# DK_D1_RS232_V5.net
KiCad netlist of a schematic drawn in EAGLE
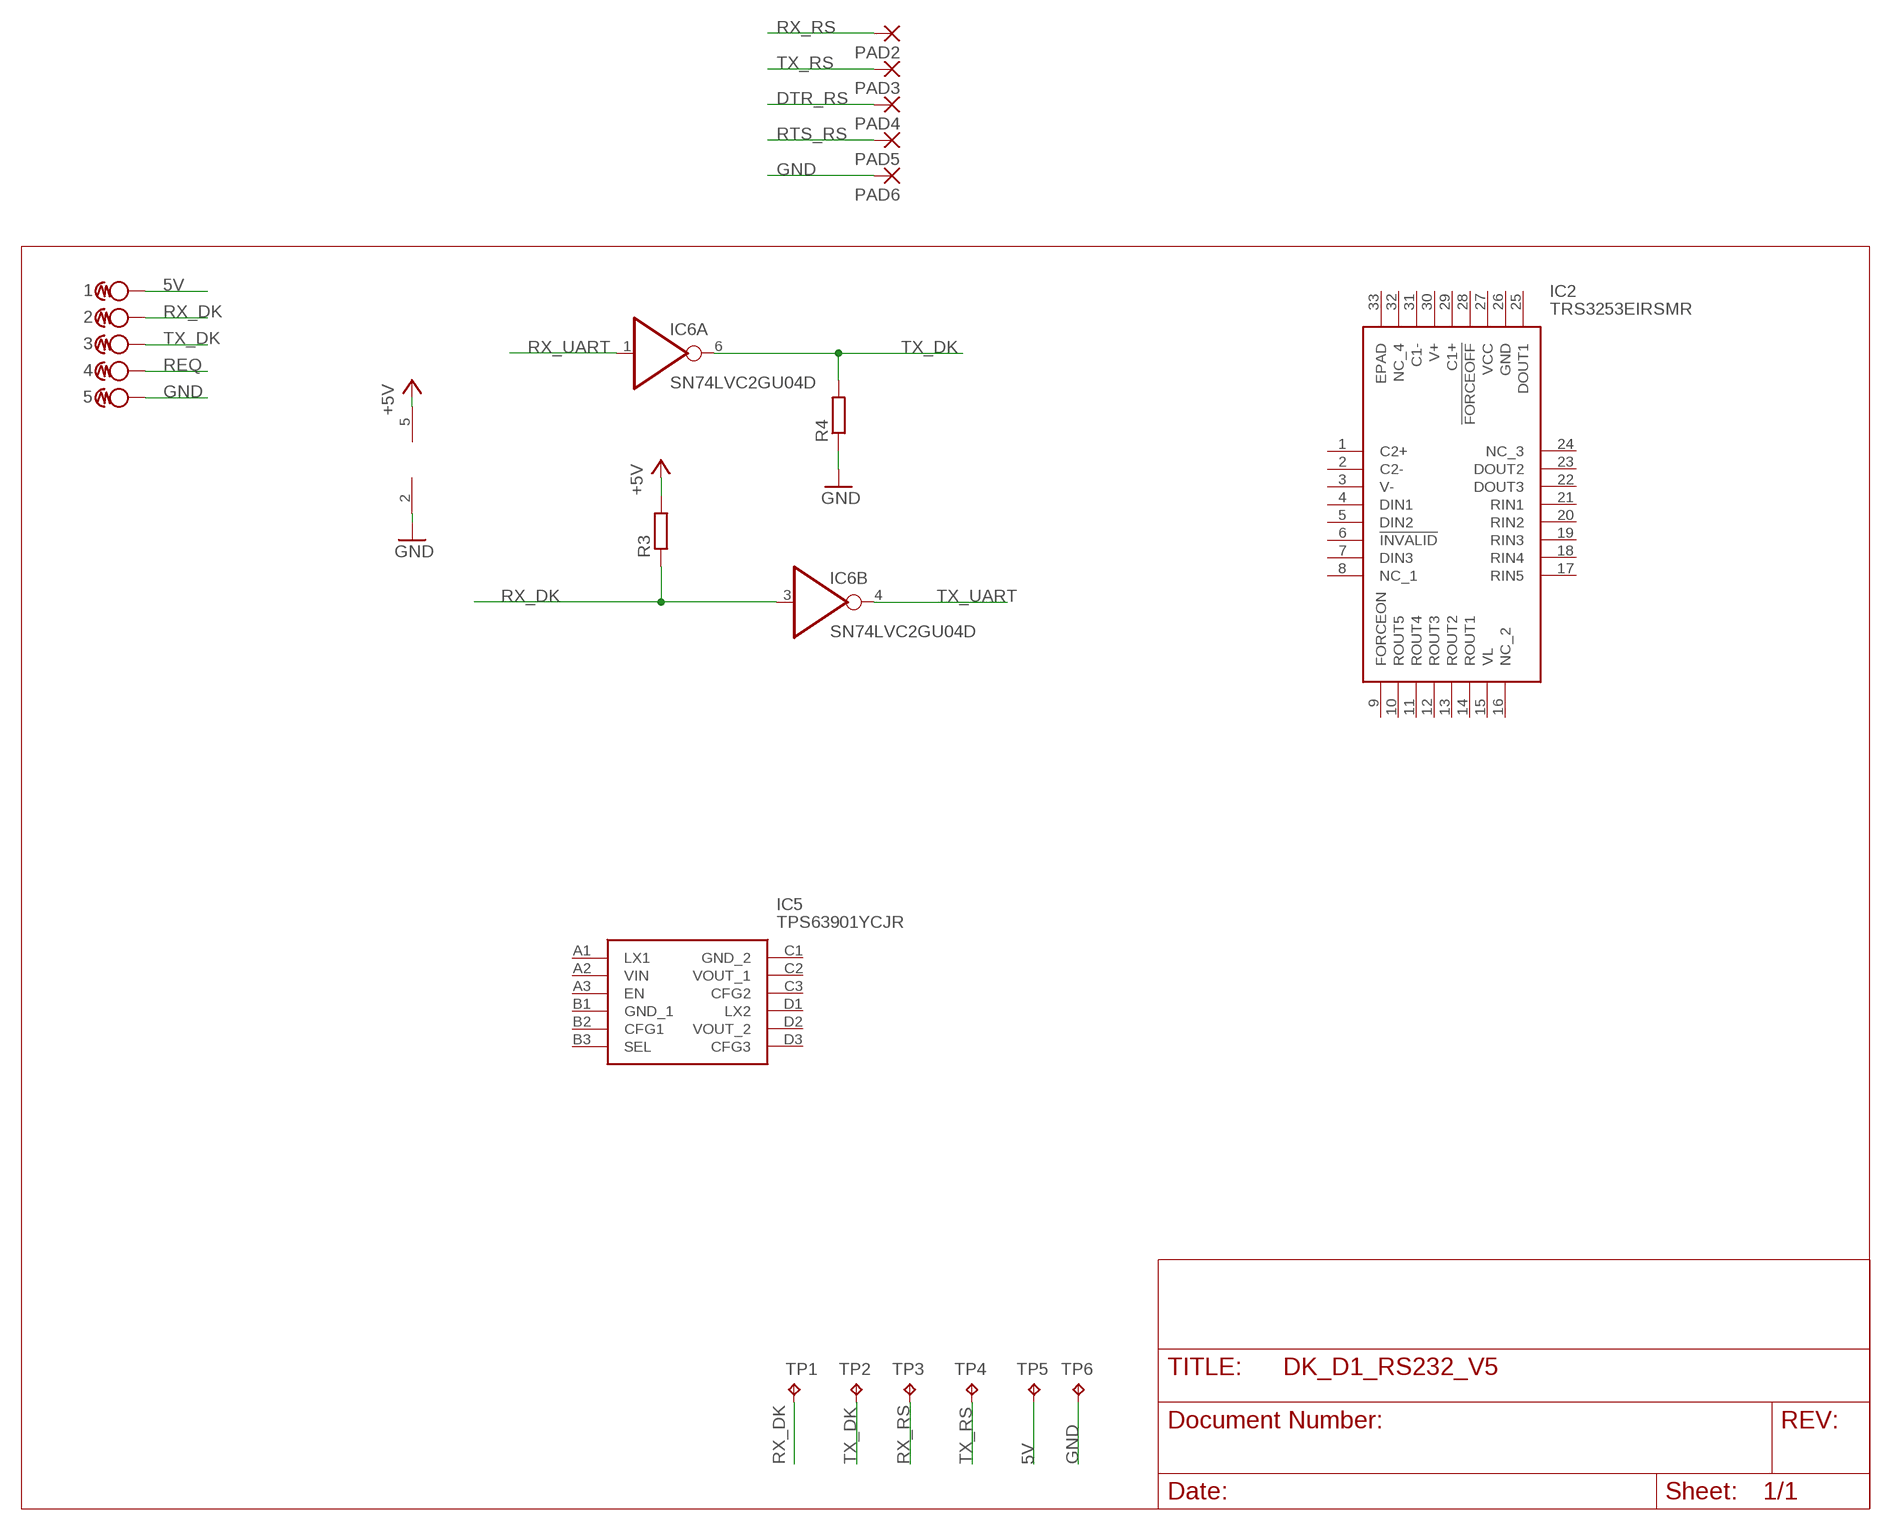
[diagram p0: schematic, sheet 1]

(export (version "E")
  (design (tool "Eeschema 10.0.6"))
  (components
    (comp (ref "1")
      (value "0975-0-15-20-80-14-11-0")
      (footprint "eagle-import:0975-0-15-20-80-14-11-0")
      (libsource (lib "eagle-import") (part "0975-0-15-20-80-14-11-0"))
    )
    (comp (ref "2")
      (value "0975-0-15-20-80-14-11-0")
      (footprint "eagle-import:0975-0-15-20-80-14-11-0")
      (libsource (lib "eagle-import") (part "0975-0-15-20-80-14-11-0"))
    )
    (comp (ref "3")
      (value "0975-0-15-20-80-14-11-0")
      (footprint "eagle-import:0975-0-15-20-80-14-11-0")
      (libsource (lib "eagle-import") (part "0975-0-15-20-80-14-11-0"))
    )
    (comp (ref "4")
      (value "0975-0-15-20-80-14-11-0")
      (footprint "eagle-import:0975-0-15-20-80-14-11-0")
      (libsource (lib "eagle-import") (part "0975-0-15-20-80-14-11-0"))
    )
    (comp (ref "5")
      (value "0975-0-15-20-80-14-11-0")
      (footprint "eagle-import:0975-0-15-20-80-14-11-0")
      (libsource (lib "eagle-import") (part "0975-0-15-20-80-14-11-0"))
    )
    (comp (ref "IC2")
      (value "TRS3253EIRSMR")
      (footprint "eagle-import:QFN40P400X400X100-33N")
      (fields (field (name "MOUSER_PART_NUMBER") "595-TRS3253EIRSMR"))
      (libsource (lib "eagle-import") (part "TRS3253EIRSMR"))
    )
    (comp (ref "IC5")
      (value "TPS63901YCJR")
      (footprint "eagle-import:BGA12C35P3X4_111X146X35")
      (fields (field (name "MOUSER_PART_NUMBER") "595-TPS63901YCJR"))
      (libsource (lib "eagle-import") (part "TPS63901YCJR"))
    )
    (comp (ref "IC6")
      (value "SN74LVC2GU04D")
      (footprint "eagle-import:DBV6")
      (libsource (lib "eagle-import") (part "SN74LVC2GU04D"))
    )
    (comp (ref "PAD2")
      (value "1,6/0,8")
      (footprint "eagle-import:1,6_0,8")
      (libsource (lib "eagle-import") (part "1,6/0,8"))
    )
    (comp (ref "PAD3")
      (value "1,6/0,8")
      (footprint "eagle-import:1,6_0,8")
      (libsource (lib "eagle-import") (part "1,6/0,8"))
    )
    (comp (ref "PAD4")
      (value "1,6/0,8")
      (footprint "eagle-import:1,6_0,8")
      (libsource (lib "eagle-import") (part "1,6/0,8"))
    )
    (comp (ref "PAD5")
      (value "1,6/0,8")
      (footprint "eagle-import:1,6_0,8")
      (libsource (lib "eagle-import") (part "1,6/0,8"))
    )
    (comp (ref "PAD6")
      (value "1,6/0,8")
      (footprint "eagle-import:1,6_0,8")
      (libsource (lib "eagle-import") (part "1,6/0,8"))
    )
    (comp (ref "R3")
      (value "R-EU_R0603")
      (footprint "eagle-import:R0603")
      (libsource (lib "eagle-import") (part "R-EU_R0603"))
    )
    (comp (ref "R4")
      (value "R-EU_R0603")
      (footprint "eagle-import:R0603")
      (libsource (lib "eagle-import") (part "R-EU_R0603"))
    )
    (comp (ref "TP1")
      (value "TPB1,27")
      (footprint "eagle-import:B1,27")
      (libsource (lib "eagle-import") (part "TPB1,27"))
    )
    (comp (ref "TP2")
      (value "TPB1,27")
      (footprint "eagle-import:B1,27")
      (libsource (lib "eagle-import") (part "TPB1,27"))
    )
    (comp (ref "TP3")
      (value "TPB1,27")
      (footprint "eagle-import:B1,27")
      (libsource (lib "eagle-import") (part "TPB1,27"))
    )
    (comp (ref "TP4")
      (value "TPB1,27")
      (footprint "eagle-import:B1,27")
      (libsource (lib "eagle-import") (part "TPB1,27"))
    )
    (comp (ref "TP5")
      (value "TPB1,27")
      (footprint "eagle-import:B1,27")
      (libsource (lib "eagle-import") (part "TPB1,27"))
    )
    (comp (ref "TP6")
      (value "TPB1,27")
      (footprint "eagle-import:B1,27")
      (libsource (lib "eagle-import") (part "TPB1,27"))
    )
  )
  (nets
    (net (code "1") (name "+5V") (class "Default")
      (node (ref "IC6") (pin "5") (pinfunction "5V_5") (pintype "bidirectional"))
      (node (ref "R3") (pin "2") (pinfunction "2_2") (pintype "passive"))
    )
    (net (code "2") (name "/5V") (class "Default")
      (node (ref "1") (pin "P$1") (pinfunction "P$1_P$1") (pintype "bidirectional"))
      (node (ref "TP5") (pin "TP") (pinfunction "TP_TP") (pintype "input"))
    )
    (net (code "3") (name "/DTR_RS") (class "Default")
      (node (ref "PAD4") (pin "1") (pinfunction "P_1") (pintype "passive"))
    )
    (net (code "4") (name "/REQ") (class "Default")
      (node (ref "4") (pin "P$1") (pinfunction "P$1_P$1") (pintype "bidirectional"))
    )
    (net (code "5") (name "/RTS_RS") (class "Default")
      (node (ref "PAD5") (pin "1") (pinfunction "P_1") (pintype "passive"))
    )
    (net (code "6") (name "/RX_DK") (class "Default")
      (node (ref "2") (pin "P$1") (pinfunction "P$1_P$1") (pintype "bidirectional"))
      (node (ref "IC6") (pin "3") (pinfunction "A_3") (pintype "output"))
      (node (ref "R3") (pin "1") (pinfunction "1_1") (pintype "passive"))
      (node (ref "TP1") (pin "TP") (pinfunction "TP_TP") (pintype "input"))
    )
    (net (code "7") (name "/RX_RS") (class "Default")
      (node (ref "PAD2") (pin "1") (pinfunction "P_1") (pintype "passive"))
      (node (ref "TP3") (pin "TP") (pinfunction "TP_TP") (pintype "input"))
    )
    (net (code "8") (name "/RX_UART") (class "Default")
      (node (ref "IC6") (pin "1") (pinfunction "A_1") (pintype "output"))
    )
    (net (code "9") (name "/TX_DK") (class "Default")
      (node (ref "3") (pin "P$1") (pinfunction "P$1_P$1") (pintype "bidirectional"))
      (node (ref "IC6") (pin "6") (pinfunction "Y_6") (pintype "output"))
      (node (ref "R4") (pin "2") (pinfunction "2_2") (pintype "passive"))
      (node (ref "TP2") (pin "TP") (pinfunction "TP_TP") (pintype "input"))
    )
    (net (code "10") (name "/TX_RS") (class "Default")
      (node (ref "PAD3") (pin "1") (pinfunction "P_1") (pintype "passive"))
      (node (ref "TP4") (pin "TP") (pinfunction "TP_TP") (pintype "input"))
    )
    (net (code "11") (name "/TX_UART") (class "Default")
      (node (ref "IC6") (pin "4") (pinfunction "Y_4") (pintype "output"))
    )
    (net (code "12") (name "GND") (class "Default")
      (node (ref "5") (pin "P$1") (pinfunction "P$1_P$1") (pintype "bidirectional"))
      (node (ref "IC6") (pin "2") (pinfunction "GND_2") (pintype "bidirectional"))
      (node (ref "PAD6") (pin "1") (pinfunction "P_1") (pintype "passive"))
      (node (ref "R4") (pin "1") (pinfunction "1_1") (pintype "passive"))
      (node (ref "TP6") (pin "TP") (pinfunction "TP_TP") (pintype "input"))
    )
    (net (code "13") (name "unconnected-(IC2-C1+-Pad29)") (class "Default")
      (node (ref "IC2") (pin "29") (pinfunction "C1+_29") (pintype "bidirectional"))
    )
    (net (code "14") (name "unconnected-(IC2-C1--Pad31)") (class "Default")
      (node (ref "IC2") (pin "31") (pinfunction "C1-_31") (pintype "bidirectional"))
    )
    (net (code "15") (name "unconnected-(IC2-C2+-Pad1)") (class "Default")
      (node (ref "IC2") (pin "1") (pinfunction "C2+_1") (pintype "bidirectional"))
    )
    (net (code "16") (name "unconnected-(IC2-C2--Pad2)") (class "Default")
      (node (ref "IC2") (pin "2") (pinfunction "C2-_2") (pintype "bidirectional"))
    )
    (net (code "17") (name "unconnected-(IC2-DIN1-Pad4)") (class "Default")
      (node (ref "IC2") (pin "4") (pinfunction "DIN1_4") (pintype "bidirectional"))
    )
    (net (code "18") (name "unconnected-(IC2-DIN2-Pad5)") (class "Default")
      (node (ref "IC2") (pin "5") (pinfunction "DIN2_5") (pintype "bidirectional"))
    )
    (net (code "19") (name "unconnected-(IC2-DIN3-Pad7)") (class "Default")
      (node (ref "IC2") (pin "7") (pinfunction "DIN3_7") (pintype "bidirectional"))
    )
    (net (code "20") (name "unconnected-(IC2-DOUT1-Pad25)") (class "Default")
      (node (ref "IC2") (pin "25") (pinfunction "DOUT1_25") (pintype "bidirectional"))
    )
    (net (code "21") (name "unconnected-(IC2-DOUT2-Pad23)") (class "Default")
      (node (ref "IC2") (pin "23") (pinfunction "DOUT2_23") (pintype "bidirectional"))
    )
    (net (code "22") (name "unconnected-(IC2-DOUT3-Pad22)") (class "Default")
      (node (ref "IC2") (pin "22") (pinfunction "DOUT3_22") (pintype "bidirectional"))
    )
    (net (code "23") (name "unconnected-(IC2-EPAD-Pad33)") (class "Default")
      (node (ref "IC2") (pin "33") (pinfunction "EPAD_33") (pintype "bidirectional"))
    )
    (net (code "24") (name "unconnected-(IC2-FORCEON-Pad9)") (class "Default")
      (node (ref "IC2") (pin "9") (pinfunction "FORCEON_9") (pintype "bidirectional"))
    )
    (net (code "25") (name "unconnected-(IC2-GND-Pad26)") (class "Default")
      (node (ref "IC2") (pin "26") (pinfunction "GND_26") (pintype "bidirectional"))
    )
    (net (code "26") (name "unconnected-(IC2-NC_1-Pad8)") (class "Default")
      (node (ref "IC2") (pin "8") (pinfunction "NC_1_8") (pintype "bidirectional"))
    )
    (net (code "27") (name "unconnected-(IC2-NC_2-Pad16)") (class "Default")
      (node (ref "IC2") (pin "16") (pinfunction "NC_2_16") (pintype "bidirectional"))
    )
    (net (code "28") (name "unconnected-(IC2-NC_3-Pad24)") (class "Default")
      (node (ref "IC2") (pin "24") (pinfunction "NC_3_24") (pintype "bidirectional"))
    )
    (net (code "29") (name "unconnected-(IC2-NC_4-Pad32)") (class "Default")
      (node (ref "IC2") (pin "32") (pinfunction "NC_4_32") (pintype "bidirectional"))
    )
    (net (code "30") (name "unconnected-(IC2-RIN1-Pad21)") (class "Default")
      (node (ref "IC2") (pin "21") (pinfunction "RIN1_21") (pintype "bidirectional"))
    )
    (net (code "31") (name "unconnected-(IC2-RIN2-Pad20)") (class "Default")
      (node (ref "IC2") (pin "20") (pinfunction "RIN2_20") (pintype "bidirectional"))
    )
    (net (code "32") (name "unconnected-(IC2-RIN3-Pad19)") (class "Default")
      (node (ref "IC2") (pin "19") (pinfunction "RIN3_19") (pintype "bidirectional"))
    )
    (net (code "33") (name "unconnected-(IC2-RIN4-Pad18)") (class "Default")
      (node (ref "IC2") (pin "18") (pinfunction "RIN4_18") (pintype "bidirectional"))
    )
    (net (code "34") (name "unconnected-(IC2-RIN5-Pad17)") (class "Default")
      (node (ref "IC2") (pin "17") (pinfunction "RIN5_17") (pintype "bidirectional"))
    )
    (net (code "35") (name "unconnected-(IC2-ROUT1-Pad14)") (class "Default")
      (node (ref "IC2") (pin "14") (pinfunction "ROUT1_14") (pintype "bidirectional"))
    )
    (net (code "36") (name "unconnected-(IC2-ROUT2-Pad13)") (class "Default")
      (node (ref "IC2") (pin "13") (pinfunction "ROUT2_13") (pintype "bidirectional"))
    )
    (net (code "37") (name "unconnected-(IC2-ROUT3-Pad12)") (class "Default")
      (node (ref "IC2") (pin "12") (pinfunction "ROUT3_12") (pintype "bidirectional"))
    )
    (net (code "38") (name "unconnected-(IC2-ROUT4-Pad11)") (class "Default")
      (node (ref "IC2") (pin "11") (pinfunction "ROUT4_11") (pintype "bidirectional"))
    )
    (net (code "39") (name "unconnected-(IC2-ROUT5-Pad10)") (class "Default")
      (node (ref "IC2") (pin "10") (pinfunction "ROUT5_10") (pintype "bidirectional"))
    )
    (net (code "40") (name "unconnected-(IC2-V+-Pad30)") (class "Default")
      (node (ref "IC2") (pin "30") (pinfunction "V+_30") (pintype "bidirectional"))
    )
    (net (code "41") (name "unconnected-(IC2-V--Pad3)") (class "Default")
      (node (ref "IC2") (pin "3") (pinfunction "V-_3") (pintype "bidirectional"))
    )
    (net (code "42") (name "unconnected-(IC2-VCC-Pad27)") (class "Default")
      (node (ref "IC2") (pin "27") (pinfunction "VCC_27") (pintype "bidirectional"))
    )
    (net (code "43") (name "unconnected-(IC2-VL-Pad15)") (class "Default")
      (node (ref "IC2") (pin "15") (pinfunction "VL_15") (pintype "bidirectional"))
    )
    (net (code "44") (name "unconnected-(IC2-~{FORCEOFF}-Pad28)") (class "Default")
      (node (ref "IC2") (pin "28") (pinfunction "~{FORCEOFF}_28") (pintype "bidirectional"))
    )
    (net (code "45") (name "unconnected-(IC2-~{INVALID}-Pad6)") (class "Default")
      (node (ref "IC2") (pin "6") (pinfunction "~{INVALID}_6") (pintype "bidirectional"))
    )
    (net (code "46") (name "unconnected-(IC5-CFG1-PadB2)") (class "Default")
      (node (ref "IC5") (pin "B2") (pinfunction "CFG1_B2") (pintype "bidirectional"))
    )
    (net (code "47") (name "unconnected-(IC5-CFG2-PadC3)") (class "Default")
      (node (ref "IC5") (pin "C3") (pinfunction "CFG2_C3") (pintype "bidirectional"))
    )
    (net (code "48") (name "unconnected-(IC5-CFG3-PadD3)") (class "Default")
      (node (ref "IC5") (pin "D3") (pinfunction "CFG3_D3") (pintype "bidirectional"))
    )
    (net (code "49") (name "unconnected-(IC5-EN-PadA3)") (class "Default")
      (node (ref "IC5") (pin "A3") (pinfunction "EN_A3") (pintype "bidirectional"))
    )
    (net (code "50") (name "unconnected-(IC5-GND_1-PadB1)") (class "Default")
      (node (ref "IC5") (pin "B1") (pinfunction "GND_1_B1") (pintype "bidirectional"))
    )
    (net (code "51") (name "unconnected-(IC5-GND_2-PadC1)") (class "Default")
      (node (ref "IC5") (pin "C1") (pinfunction "GND_2_C1") (pintype "bidirectional"))
    )
    (net (code "52") (name "unconnected-(IC5-LX1-PadA1)") (class "Default")
      (node (ref "IC5") (pin "A1") (pinfunction "LX1_A1") (pintype "bidirectional"))
    )
    (net (code "53") (name "unconnected-(IC5-LX2-PadD1)") (class "Default")
      (node (ref "IC5") (pin "D1") (pinfunction "LX2_D1") (pintype "bidirectional"))
    )
    (net (code "54") (name "unconnected-(IC5-SEL-PadB3)") (class "Default")
      (node (ref "IC5") (pin "B3") (pinfunction "SEL_B3") (pintype "bidirectional"))
    )
    (net (code "55") (name "unconnected-(IC5-VIN-PadA2)") (class "Default")
      (node (ref "IC5") (pin "A2") (pinfunction "VIN_A2") (pintype "bidirectional"))
    )
    (net (code "56") (name "unconnected-(IC5-VOUT_1-PadC2)") (class "Default")
      (node (ref "IC5") (pin "C2") (pinfunction "VOUT_1_C2") (pintype "bidirectional"))
    )
    (net (code "57") (name "unconnected-(IC5-VOUT_2-PadD2)") (class "Default")
      (node (ref "IC5") (pin "D2") (pinfunction "VOUT_2_D2") (pintype "bidirectional"))
    )
  )
)
